# DobbelSteen_with_programing_header_revis.net
KiCad netlist of a schematic drawn in EAGLE
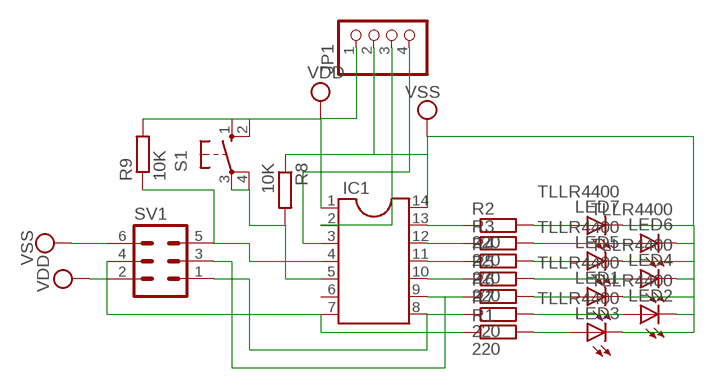
[diagram p0: schematic, sheet 1]

(export (version "E")
  (design (tool "Eeschema 10.0.6"))
  (components
    (comp (ref "IC1")
      (value "DIL14S")
      (footprint "eagle-import:SOCKET-14")
      (libsource (lib "eagle-import") (part "DIL14S"))
    )
    (comp (ref "JP1")
      (value "PINHD-1X4")
      (footprint "eagle-import:1X04")
      (libsource (lib "eagle-import") (part "PINHD-1X4"))
    )
    (comp (ref "LED1")
      (value "TLLR4400")
      (footprint "eagle-import:LED3MM")
      (fields (field (name "MF") "VISHAY SEMICONDUCTOR"))
      (libsource (lib "eagle-import") (part "TLLR4400"))
    )
    (comp (ref "LED2")
      (value "TLLR4400")
      (footprint "eagle-import:LED3MM")
      (fields (field (name "MF") "VISHAY SEMICONDUCTOR"))
      (libsource (lib "eagle-import") (part "TLLR4400"))
    )
    (comp (ref "LED3")
      (value "TLLR4400")
      (footprint "eagle-import:LED3MM")
      (fields (field (name "MF") "VISHAY SEMICONDUCTOR"))
      (libsource (lib "eagle-import") (part "TLLR4400"))
    )
    (comp (ref "LED4")
      (value "TLLR4400")
      (footprint "eagle-import:LED3MM")
      (fields (field (name "MF") "VISHAY SEMICONDUCTOR"))
      (libsource (lib "eagle-import") (part "TLLR4400"))
    )
    (comp (ref "LED5")
      (value "TLLR4400")
      (footprint "eagle-import:LED3MM")
      (fields (field (name "MF") "VISHAY SEMICONDUCTOR"))
      (libsource (lib "eagle-import") (part "TLLR4400"))
    )
    (comp (ref "LED6")
      (value "TLLR4400")
      (footprint "eagle-import:LED3MM")
      (fields (field (name "MF") "VISHAY SEMICONDUCTOR"))
      (libsource (lib "eagle-import") (part "TLLR4400"))
    )
    (comp (ref "LED7")
      (value "TLLR4400")
      (footprint "eagle-import:LED3MM")
      (fields (field (name "MF") "VISHAY SEMICONDUCTOR"))
      (libsource (lib "eagle-import") (part "TLLR4400"))
    )
    (comp (ref "R1")
      (value "220")
      (footprint "eagle-import:0204_7")
      (libsource (lib "eagle-import") (part "R0204/7"))
    )
    (comp (ref "R2")
      (value "220")
      (footprint "eagle-import:0204_7")
      (libsource (lib "eagle-import") (part "R0204/7"))
    )
    (comp (ref "R3")
      (value "220")
      (footprint "eagle-import:0204_7")
      (libsource (lib "eagle-import") (part "R0204/7"))
    )
    (comp (ref "R4")
      (value "220")
      (footprint "eagle-import:0204_7")
      (libsource (lib "eagle-import") (part "R0204/7"))
    )
    (comp (ref "R5")
      (value "220")
      (footprint "eagle-import:0204_7")
      (libsource (lib "eagle-import") (part "R0204/7"))
    )
    (comp (ref "R6")
      (value "R0204/7")
      (footprint "eagle-import:0204_7")
      (libsource (lib "eagle-import") (part "R0204/7"))
    )
    (comp (ref "R7")
      (value "220")
      (footprint "eagle-import:0204_7")
      (libsource (lib "eagle-import") (part "R0204/7"))
    )
    (comp (ref "R8")
      (value "10K")
      (footprint "eagle-import:0204_7")
      (libsource (lib "eagle-import") (part "R0204/7"))
    )
    (comp (ref "R9")
      (value "10K")
      (footprint "eagle-import:0204_7")
      (libsource (lib "eagle-import") (part "R0204/7"))
    )
    (comp (ref "S1")
      (value "10-XX")
      (footprint "eagle-import:B3F-10XX")
      (fields (field (name "MPN") "B3F-1000"))
      (libsource (lib "eagle-import") (part "10-XX"))
    )
    (comp (ref "SV1")
      (value "MA03-2")
      (footprint "eagle-import:MA03-2")
      (libsource (lib "eagle-import") (part "MA03-2"))
    )
  )
  (nets
    (net (code "1") (name "Net-(IC1-Pad2)") (class "Default")
      (node (ref "IC1") (pin "2") (pinfunction "2_2") (pintype "passive"))
      (node (ref "JP1") (pin "3") (pinfunction "3_3") (pintype "passive"))
    )
    (net (code "2") (name "Net-(IC1-Pad3)") (class "Default")
      (node (ref "IC1") (pin "3") (pinfunction "3_3") (pintype "passive"))
      (node (ref "JP1") (pin "4") (pinfunction "4_4") (pintype "passive"))
    )
    (net (code "3") (name "Net-(IC1-Pad4)") (class "Default")
      (node (ref "IC1") (pin "4") (pinfunction "4_4") (pintype "passive"))
      (node (ref "R9") (pin "1") (pinfunction "1_1") (pintype "passive"))
      (node (ref "SV1") (pin "5") (pinfunction "5_5") (pintype "passive"))
    )
    (net (code "4") (name "Net-(IC1-Pad7)") (class "Default")
      (node (ref "IC1") (pin "7") (pinfunction "7_7") (pintype "passive"))
      (node (ref "R1") (pin "1") (pinfunction "1_1") (pintype "passive"))
      (node (ref "SV1") (pin "4") (pinfunction "4_4") (pintype "passive"))
    )
    (net (code "5") (name "Net-(IC1-Pad8)") (class "Default")
      (node (ref "IC1") (pin "8") (pinfunction "8_8") (pintype "passive"))
      (node (ref "R7") (pin "1") (pinfunction "1_1") (pintype "passive"))
      (node (ref "SV1") (pin "1") (pinfunction "1_1") (pintype "passive"))
    )
    (net (code "6") (name "Net-(IC1-Pad9)") (class "Default")
      (node (ref "IC1") (pin "9") (pinfunction "9_9") (pintype "passive"))
      (node (ref "R6") (pin "1") (pinfunction "1_1") (pintype "passive"))
      (node (ref "SV1") (pin "3") (pinfunction "3_3") (pintype "passive"))
    )
    (net (code "7") (name "Net-(IC1-Pad10)") (class "Default")
      (node (ref "IC1") (pin "10") (pinfunction "10_10") (pintype "passive"))
      (node (ref "R5") (pin "1") (pinfunction "1_1") (pintype "passive"))
    )
    (net (code "8") (name "Net-(IC1-Pad11)") (class "Default")
      (node (ref "IC1") (pin "11") (pinfunction "11_11") (pintype "passive"))
      (node (ref "R4") (pin "1") (pinfunction "1_1") (pintype "passive"))
    )
    (net (code "9") (name "Net-(IC1-Pad12)") (class "Default")
      (node (ref "IC1") (pin "12") (pinfunction "12_12") (pintype "passive"))
      (node (ref "R3") (pin "1") (pinfunction "1_1") (pintype "passive"))
    )
    (net (code "10") (name "Net-(IC1-Pad13)") (class "Default")
      (node (ref "IC1") (pin "13") (pinfunction "13_13") (pintype "passive"))
      (node (ref "R2") (pin "1") (pinfunction "1_1") (pintype "passive"))
    )
    (net (code "11") (name "Net-(LED1-PadA)") (class "Default")
      (node (ref "LED1") (pin "A") (pinfunction "A_A") (pintype "passive"))
      (node (ref "R6") (pin "2") (pinfunction "2_2") (pintype "passive"))
    )
    (net (code "12") (name "Net-(LED2-PadA)") (class "Default")
      (node (ref "LED2") (pin "A") (pinfunction "A_A") (pintype "passive"))
      (node (ref "R7") (pin "2") (pinfunction "2_2") (pintype "passive"))
    )
    (net (code "13") (name "Net-(LED3-PadA)") (class "Default")
      (node (ref "LED3") (pin "A") (pinfunction "A_A") (pintype "passive"))
      (node (ref "R1") (pin "2") (pinfunction "2_2") (pintype "passive"))
    )
    (net (code "14") (name "Net-(LED4-PadA)") (class "Default")
      (node (ref "LED4") (pin "A") (pinfunction "A_A") (pintype "passive"))
      (node (ref "R5") (pin "2") (pinfunction "2_2") (pintype "passive"))
    )
    (net (code "15") (name "Net-(LED5-PadA)") (class "Default")
      (node (ref "LED5") (pin "A") (pinfunction "A_A") (pintype "passive"))
      (node (ref "R4") (pin "2") (pinfunction "2_2") (pintype "passive"))
    )
    (net (code "16") (name "Net-(LED6-PadA)") (class "Default")
      (node (ref "LED6") (pin "A") (pinfunction "A_A") (pintype "passive"))
      (node (ref "R3") (pin "2") (pinfunction "2_2") (pintype "passive"))
    )
    (net (code "17") (name "Net-(LED7-PadA)") (class "Default")
      (node (ref "LED7") (pin "A") (pinfunction "A_A") (pintype "passive"))
      (node (ref "R2") (pin "2") (pinfunction "2_2") (pintype "passive"))
    )
    (net (code "18") (name "Net-(S1-P)") (class "Default")
      (node (ref "IC1") (pin "5") (pinfunction "5_5") (pintype "passive"))
      (node (ref "R8") (pin "2") (pinfunction "2_2") (pintype "passive"))
      (node (ref "S1") (pin "3") (pinfunction "P_3") (pintype "passive"))
      (node (ref "S1") (pin "4") (pinfunction "P1_4") (pintype "passive"))
    )
    (net (code "19") (name "VDD") (class "Default")
      (node (ref "IC1") (pin "1") (pinfunction "1_1") (pintype "passive"))
      (node (ref "JP1") (pin "1") (pinfunction "1_1") (pintype "passive"))
      (node (ref "R9") (pin "2") (pinfunction "2_2") (pintype "passive"))
      (node (ref "S1") (pin "1") (pinfunction "S_1") (pintype "passive"))
      (node (ref "S1") (pin "2") (pinfunction "S1_2") (pintype "passive"))
      (node (ref "SV1") (pin "2") (pinfunction "2_2") (pintype "passive"))
    )
    (net (code "20") (name "VSS") (class "Default")
      (node (ref "IC1") (pin "14") (pinfunction "14_14") (pintype "passive"))
      (node (ref "JP1") (pin "2") (pinfunction "2_2") (pintype "passive"))
      (node (ref "LED1") (pin "K") (pinfunction "C_K") (pintype "passive"))
      (node (ref "LED2") (pin "K") (pinfunction "C_K") (pintype "passive"))
      (node (ref "LED3") (pin "K") (pinfunction "C_K") (pintype "passive"))
      (node (ref "LED4") (pin "K") (pinfunction "C_K") (pintype "passive"))
      (node (ref "LED5") (pin "K") (pinfunction "C_K") (pintype "passive"))
      (node (ref "LED6") (pin "K") (pinfunction "C_K") (pintype "passive"))
      (node (ref "LED7") (pin "K") (pinfunction "C_K") (pintype "passive"))
      (node (ref "R8") (pin "1") (pinfunction "1_1") (pintype "passive"))
      (node (ref "SV1") (pin "6") (pinfunction "6_6") (pintype "passive"))
    )
    (net (code "21") (name "unconnected-(IC1-Pad6)") (class "Default")
      (node (ref "IC1") (pin "6") (pinfunction "6_6") (pintype "passive"))
    )
  )
)
